# VNH2SP30e.net
KiCad netlist of a schematic drawn in EAGLE
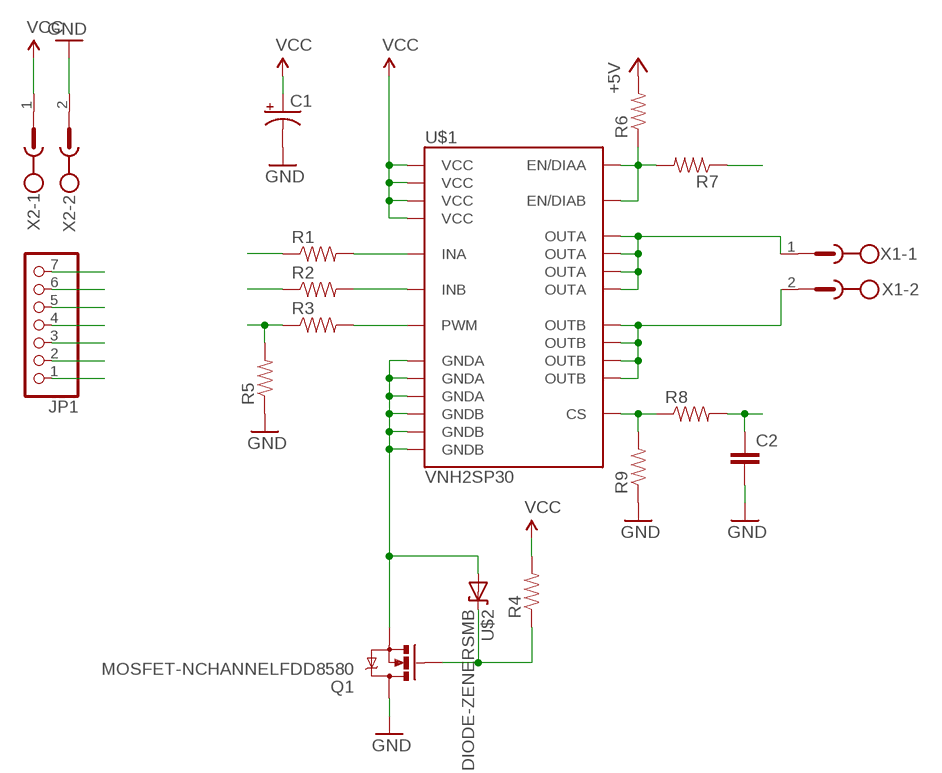
[diagram p0: schematic, sheet 1]

(export (version "E")
  (design (tool "Eeschema 10.0.6"))
  (components
    (comp (ref "C1")
      (value "CAP_POLG")
      (footprint "eagle-import:PANASONIC_G")
      (libsource (lib "eagle-import") (part "CAP_POLG"))
    )
    (comp (ref "C2")
      (value "CAP1206")
      (footprint "eagle-import:1206")
      (libsource (lib "eagle-import") (part "CAP1206"))
    )
    (comp (ref "JP1")
      (value "PINHD-1X7")
      (footprint "eagle-import:1X07")
      (libsource (lib "eagle-import") (part "PINHD-1X7"))
    )
    (comp (ref "Q1")
      (value "MOSFET-NCHANNELFDD8580")
      (footprint "eagle-import:DPAK")
      (libsource (lib "eagle-import") (part "MOSFET-NCHANNELFDD8580"))
    )
    (comp (ref "R1")
      (value "RESISTOR1206")
      (footprint "eagle-import:1206")
      (libsource (lib "eagle-import") (part "RESISTOR1206"))
    )
    (comp (ref "R2")
      (value "RESISTOR1206")
      (footprint "eagle-import:1206")
      (libsource (lib "eagle-import") (part "RESISTOR1206"))
    )
    (comp (ref "R3")
      (value "RESISTOR1206")
      (footprint "eagle-import:1206")
      (libsource (lib "eagle-import") (part "RESISTOR1206"))
    )
    (comp (ref "R4")
      (value "RESISTOR1206")
      (footprint "eagle-import:1206")
      (libsource (lib "eagle-import") (part "RESISTOR1206"))
    )
    (comp (ref "R5")
      (value "RESISTOR1206")
      (footprint "eagle-import:1206")
      (libsource (lib "eagle-import") (part "RESISTOR1206"))
    )
    (comp (ref "R6")
      (value "RESISTOR1206")
      (footprint "eagle-import:1206")
      (libsource (lib "eagle-import") (part "RESISTOR1206"))
    )
    (comp (ref "R7")
      (value "RESISTOR1206")
      (footprint "eagle-import:1206")
      (libsource (lib "eagle-import") (part "RESISTOR1206"))
    )
    (comp (ref "R8")
      (value "RESISTOR1206")
      (footprint "eagle-import:1206")
      (libsource (lib "eagle-import") (part "RESISTOR1206"))
    )
    (comp (ref "R9")
      (value "RESISTOR1206")
      (footprint "eagle-import:1206")
      (libsource (lib "eagle-import") (part "RESISTOR1206"))
    )
    (comp (ref "U$1")
      (value "VNH2SP30")
      (footprint "eagle-import:VNH2SP30")
      (libsource (lib "eagle-import") (part "VNH2SP30"))
    )
    (comp (ref "U$2")
      (value "DIODE-ZENERSMB")
      (footprint "eagle-import:SMB-DIODE")
      (libsource (lib "eagle-import") (part "DIODE-ZENERSMB"))
    )
    (comp (ref "X1")
      (value "MSTBV2")
      (footprint "eagle-import:MSTBV2")
      (libsource (lib "eagle-import") (part "MSTBV2"))
    )
    (comp (ref "X2")
      (value "MSTBV2")
      (footprint "eagle-import:MSTBV2")
      (libsource (lib "eagle-import") (part "MSTBV2"))
    )
  )
  (nets
    (net (code "1") (name "+5V") (class "Default")
      (node (ref "JP1") (pin "7") (pinfunction "7_7") (pintype "passive"))
      (node (ref "R6") (pin "2") (pinfunction "2_2") (pintype "passive"))
    )
    (net (code "2") (name "/CS") (class "Default")
      (node (ref "C2") (pin "1") (pinfunction "1_1") (pintype "passive"))
      (node (ref "JP1") (pin "2") (pinfunction "2_2") (pintype "passive"))
      (node (ref "R8") (pin "2") (pinfunction "2_2") (pintype "passive"))
    )
    (net (code "3") (name "/EN") (class "Default")
      (node (ref "JP1") (pin "6") (pinfunction "6_6") (pintype "passive"))
      (node (ref "R7") (pin "1") (pinfunction "1_1") (pintype "passive"))
    )
    (net (code "4") (name "/INA") (class "Default")
      (node (ref "JP1") (pin "5") (pinfunction "5_5") (pintype "passive"))
      (node (ref "R1") (pin "1") (pinfunction "1_1") (pintype "passive"))
    )
    (net (code "5") (name "/INB") (class "Default")
      (node (ref "JP1") (pin "4") (pinfunction "4_4") (pintype "passive"))
      (node (ref "R2") (pin "1") (pinfunction "1_1") (pintype "passive"))
    )
    (net (code "6") (name "/PWM") (class "Default")
      (node (ref "JP1") (pin "3") (pinfunction "3_3") (pintype "passive"))
      (node (ref "R3") (pin "1") (pinfunction "1_1") (pintype "passive"))
      (node (ref "R5") (pin "2") (pinfunction "2_2") (pintype "passive"))
    )
    (net (code "7") (name "GND") (class "Default")
      (node (ref "C1") (pin "-") (pinfunction "-_-") (pintype "passive"))
      (node (ref "C2") (pin "2") (pinfunction "2_2") (pintype "passive"))
      (node (ref "JP1") (pin "1") (pinfunction "1_1") (pintype "passive"))
      (node (ref "Q1") (pin "4") (pinfunction "D_4") (pintype "passive"))
      (node (ref "R5") (pin "1") (pinfunction "1_1") (pintype "passive"))
      (node (ref "R9") (pin "1") (pinfunction "1_1") (pintype "passive"))
      (node (ref "X2") (pin "2") (pinfunction "SK_2") (pintype "passive"))
    )
    (net (code "8") (name "Net-(Q1-G)") (class "Default")
      (node (ref "Q1") (pin "1") (pinfunction "G_1") (pintype "passive"))
      (node (ref "R4") (pin "1") (pinfunction "1_1") (pintype "passive"))
      (node (ref "U$2") (pin "C") (pinfunction "C_C") (pintype "passive"))
    )
    (net (code "9") (name "Net-(Q1-S)") (class "Default")
      (node (ref "Q1") (pin "3") (pinfunction "S_3") (pintype "passive"))
      (node (ref "U$1") (pin "18") (pinfunction "GNDB_18") (pintype "bidirectional"))
      (node (ref "U$1") (pin "19") (pinfunction "GNDB_19") (pintype "bidirectional"))
      (node (ref "U$1") (pin "20") (pinfunction "GNDB_20") (pintype "bidirectional"))
      (node (ref "U$1") (pin "26") (pinfunction "GNDA_26") (pintype "bidirectional"))
      (node (ref "U$1") (pin "27") (pinfunction "GNDA_27") (pintype "bidirectional"))
      (node (ref "U$1") (pin "28") (pinfunction "GNDA_28") (pintype "bidirectional"))
      (node (ref "U$2") (pin "A") (pinfunction "A_A") (pintype "passive"))
    )
    (net (code "10") (name "Net-(U$1-CS)") (class "Default")
      (node (ref "R8") (pin "1") (pinfunction "1_1") (pintype "passive"))
      (node (ref "R9") (pin "2") (pinfunction "2_2") (pintype "passive"))
      (node (ref "U$1") (pin "9") (pinfunction "CS_9") (pintype "bidirectional"))
    )
    (net (code "11") (name "Net-(U$1-EN{slash}DIAA)") (class "Default")
      (node (ref "R6") (pin "1") (pinfunction "1_1") (pintype "passive"))
      (node (ref "R7") (pin "2") (pinfunction "2_2") (pintype "passive"))
      (node (ref "U$1") (pin "10") (pinfunction "EN/DIAB_10") (pintype "bidirectional"))
      (node (ref "U$1") (pin "6") (pinfunction "EN/DIAA_6") (pintype "bidirectional"))
    )
    (net (code "12") (name "Net-(U$1-INA)") (class "Default")
      (node (ref "R1") (pin "2") (pinfunction "2_2") (pintype "passive"))
      (node (ref "U$1") (pin "5") (pinfunction "INA_5") (pintype "bidirectional"))
    )
    (net (code "13") (name "Net-(U$1-INB)") (class "Default")
      (node (ref "R2") (pin "2") (pinfunction "2_2") (pintype "passive"))
      (node (ref "U$1") (pin "11") (pinfunction "INB_11") (pintype "bidirectional"))
    )
    (net (code "14") (name "Net-(U$1-PWM)") (class "Default")
      (node (ref "R3") (pin "2") (pinfunction "2_2") (pintype "passive"))
      (node (ref "U$1") (pin "8") (pinfunction "PWM_8") (pintype "bidirectional"))
    )
    (net (code "15") (name "Net-(X1A-SK)") (class "Default")
      (node (ref "U$1") (pin "1") (pinfunction "OUTA_1") (pintype "bidirectional"))
      (node (ref "U$1") (pin "25") (pinfunction "OUTA_25") (pintype "bidirectional"))
      (node (ref "U$1") (pin "30") (pinfunction "OUTA_30") (pintype "bidirectional"))
      (node (ref "U$1") (pin "SLUG3") (pinfunction "OUTA_SLUG3") (pintype "bidirectional"))
      (node (ref "X1") (pin "1") (pinfunction "SK_1") (pintype "passive"))
    )
    (net (code "16") (name "Net-(X1B-SK)") (class "Default")
      (node (ref "U$1") (pin "15") (pinfunction "OUTB_15") (pintype "bidirectional"))
      (node (ref "U$1") (pin "16") (pinfunction "OUTB_16") (pintype "bidirectional"))
      (node (ref "U$1") (pin "21") (pinfunction "OUTB_21") (pintype "bidirectional"))
      (node (ref "U$1") (pin "SLUG2") (pinfunction "OUTB_SLUG2") (pintype "bidirectional"))
      (node (ref "X1") (pin "2") (pinfunction "SK_2") (pintype "passive"))
    )
    (net (code "17") (name "VCC") (class "Default")
      (node (ref "C1") (pin "+") (pinfunction "+_+") (pintype "passive"))
      (node (ref "R4") (pin "2") (pinfunction "2_2") (pintype "passive"))
      (node (ref "U$1") (pin "13") (pinfunction "VCC_13") (pintype "bidirectional"))
      (node (ref "U$1") (pin "23") (pinfunction "VCC_23") (pintype "bidirectional"))
      (node (ref "U$1") (pin "3") (pinfunction "VCC_3") (pintype "bidirectional"))
      (node (ref "U$1") (pin "SLUG1") (pinfunction "VCC_SLUG1") (pintype "bidirectional"))
      (node (ref "X2") (pin "1") (pinfunction "SK_1") (pintype "passive"))
    )
  )
)
